# Connecors-Output.net
KiCad netlist of a schematic drawn in Altium Designer
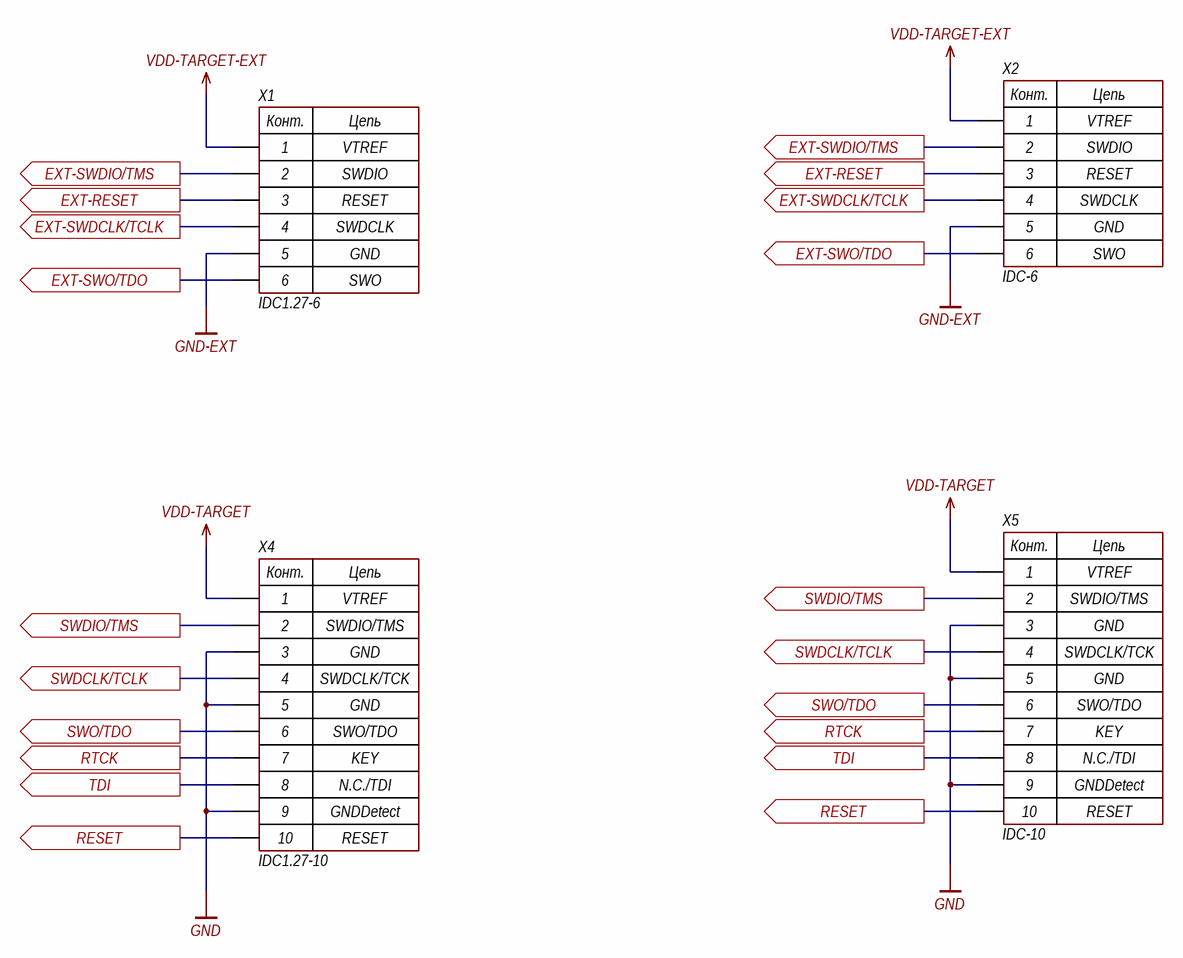
[diagram p0: Connecors-Output.SchDoc]

(export (version "E")
  (design (tool "Eeschema 10.0.6"))
  (components
    (comp (ref "X1")
      (value "IDC1.27-6")
      (footprint "CON: IDC1.27-6")
      (libsource (lib "Connectors") (part "6-Connector"))
    )
    (comp (ref "X2")
      (value "IDC-6")
      (footprint "custom:CON: IDC-6MS")
      (libsource (lib "Connectors") (part "6-Connector"))
    )
    (comp (ref "X4")
      (value "IDC1.27-10")
      (footprint "CON: IDC1.27-10")
      (libsource (lib "Connectors") (part "10-Connector"))
    )
    (comp (ref "X5")
      (value "IDC-10")
      (footprint "CON: IDC-10MS")
      (libsource (lib "Connectors") (part "10-Connector"))
    )
  )
  (nets
    (net (code "1") (name "/EXT-RESET") (class "Default")
      (node (ref "X1") (pin "3") (pinfunction "3_3") (pintype "passive"))
      (node (ref "X2") (pin "3") (pinfunction "3_3") (pintype "passive"))
    )
    (net (code "2") (name "/EXT-SWDCLK{slash}TCLK") (class "Default")
      (node (ref "X1") (pin "4") (pinfunction "4_4") (pintype "passive"))
      (node (ref "X2") (pin "4") (pinfunction "4_4") (pintype "passive"))
    )
    (net (code "3") (name "/EXT-SWDIO{slash}TMS") (class "Default")
      (node (ref "X1") (pin "2") (pinfunction "2_2") (pintype "passive"))
      (node (ref "X2") (pin "2") (pinfunction "2_2") (pintype "passive"))
    )
    (net (code "4") (name "/EXT-SWO{slash}TDO") (class "Default")
      (node (ref "X1") (pin "6") (pinfunction "6_6") (pintype "passive"))
      (node (ref "X2") (pin "6") (pinfunction "6_6") (pintype "passive"))
    )
    (net (code "5") (name "/RESET") (class "Default")
      (node (ref "X4") (pin "10") (pinfunction "10_10") (pintype "passive"))
      (node (ref "X5") (pin "10") (pinfunction "10_10") (pintype "passive"))
    )
    (net (code "6") (name "/RTCK") (class "Default")
      (node (ref "X4") (pin "7") (pinfunction "7_7") (pintype "passive"))
      (node (ref "X5") (pin "7") (pinfunction "7_7") (pintype "passive"))
    )
    (net (code "7") (name "/SWDCLK{slash}TCLK") (class "Default")
      (node (ref "X4") (pin "4") (pinfunction "4_4") (pintype "passive"))
      (node (ref "X5") (pin "4") (pinfunction "4_4") (pintype "passive"))
    )
    (net (code "8") (name "/SWDIO{slash}TMS") (class "Default")
      (node (ref "X4") (pin "2") (pinfunction "2_2") (pintype "passive"))
      (node (ref "X5") (pin "2") (pinfunction "2_2") (pintype "passive"))
    )
    (net (code "9") (name "/SWO{slash}TDO") (class "Default")
      (node (ref "X4") (pin "6") (pinfunction "6_6") (pintype "passive"))
      (node (ref "X5") (pin "6") (pinfunction "6_6") (pintype "passive"))
    )
    (net (code "10") (name "/TDI") (class "Default")
      (node (ref "X4") (pin "8") (pinfunction "8_8") (pintype "passive"))
      (node (ref "X5") (pin "8") (pinfunction "8_8") (pintype "passive"))
    )
    (net (code "11") (name "GND") (class "Default")
      (node (ref "X4") (pin "3") (pinfunction "3_3") (pintype "passive"))
      (node (ref "X4") (pin "5") (pinfunction "5_5") (pintype "passive"))
      (node (ref "X4") (pin "9") (pinfunction "9_9") (pintype "passive"))
      (node (ref "X5") (pin "3") (pinfunction "3_3") (pintype "passive"))
      (node (ref "X5") (pin "5") (pinfunction "5_5") (pintype "passive"))
      (node (ref "X5") (pin "9") (pinfunction "9_9") (pintype "passive"))
    )
    (net (code "12") (name "GND-EXT") (class "Default")
      (node (ref "X1") (pin "5") (pinfunction "5_5") (pintype "passive"))
      (node (ref "X2") (pin "5") (pinfunction "5_5") (pintype "passive"))
    )
    (net (code "13") (name "VDD-TARGET") (class "Default")
      (node (ref "X4") (pin "1") (pinfunction "1_1") (pintype "passive"))
      (node (ref "X5") (pin "1") (pinfunction "1_1") (pintype "passive"))
    )
    (net (code "14") (name "VDD-TARGET-EXT") (class "Default")
      (node (ref "X1") (pin "1") (pinfunction "1_1") (pintype "passive"))
      (node (ref "X2") (pin "1") (pinfunction "1_1") (pintype "passive"))
    )
  )
)
